# Display.net
KiCad netlist of a schematic drawn in Altium Designer
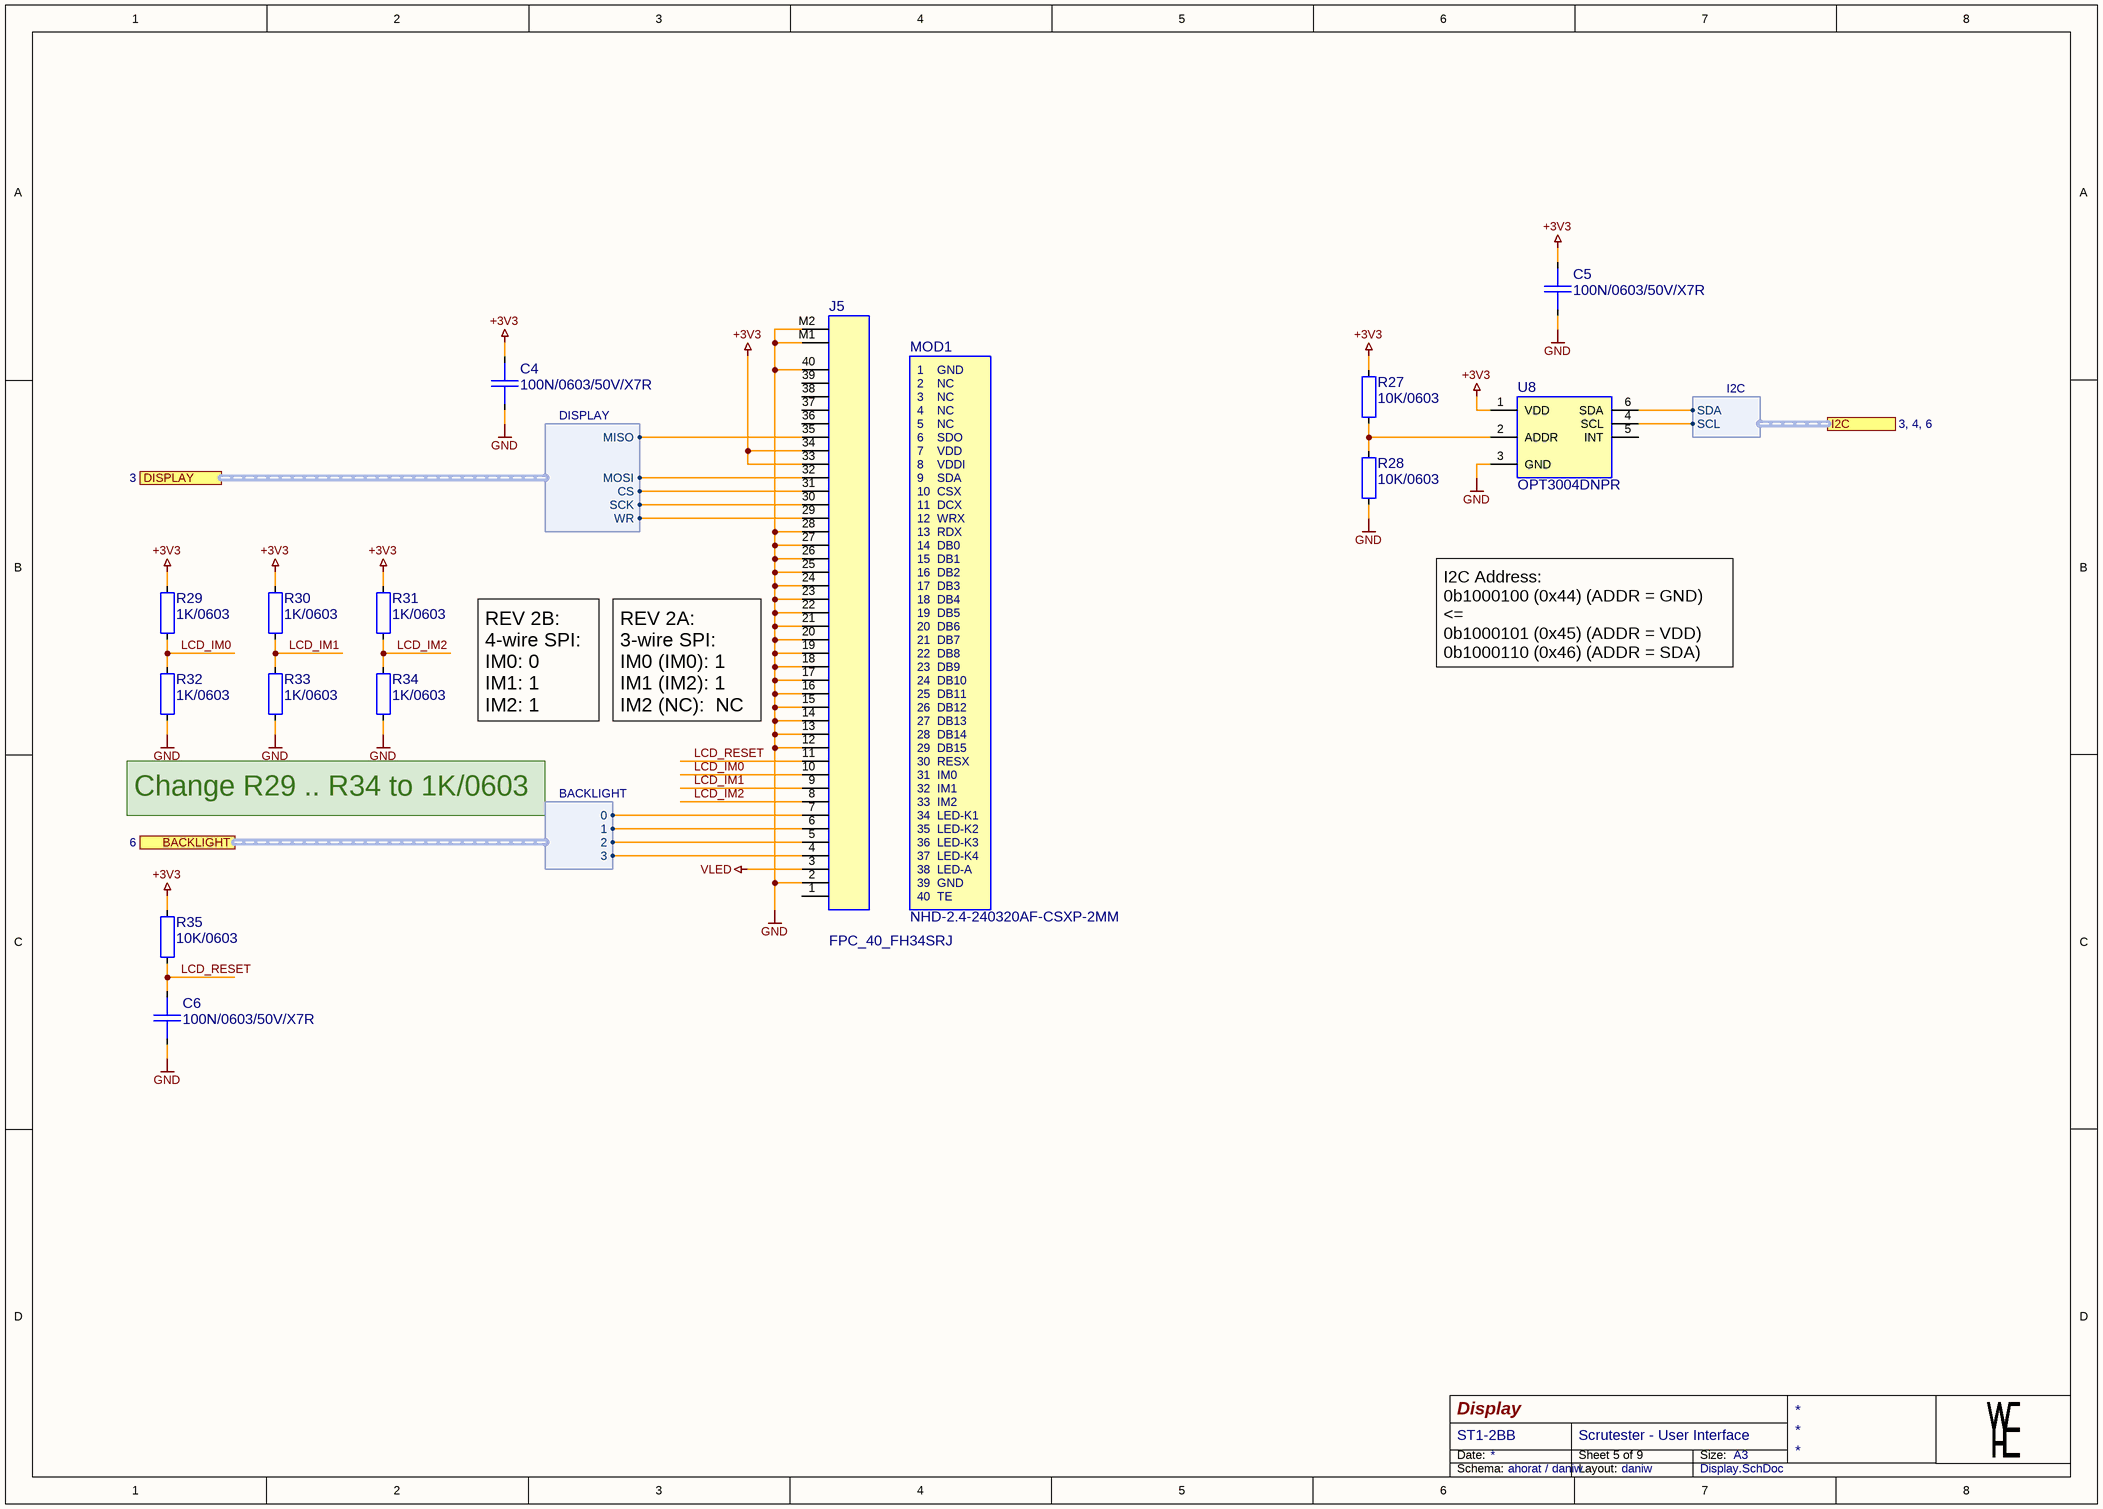
[diagram p0: Display.SchDoc]

(export (version "E")
  (design (tool "Eeschema 10.0.6"))
  (components
    (comp (ref "C4")
      (value "100N/0603/50V/X7R")
      (footprint "CAP0603_X7R")
      (description "CAP SM 0603 100nF 50V X7R")
      (fields (field (name "MANUFACTURER") "GENERIC"))
      (libsource (lib "daniw_altium_lib") (part "C"))
    )
    (comp (ref "C5")
      (value "100N/0603/50V/X7R")
      (footprint "CAP0603_X7R")
      (description "CAP SM 0603 100nF 50V X7R")
      (fields (field (name "MANUFACTURER") "GENERIC"))
      (libsource (lib "daniw_altium_lib") (part "C"))
    )
    (comp (ref "C6")
      (value "100N/0603/50V/X7R")
      (footprint "CAP0603_X7R")
      (description "CAP SM 0603 100nF 50V X7R")
      (fields (field (name "MANUFACTURER") "GENERIC"))
      (libsource (lib "daniw_altium_lib") (part "C"))
    )
    (comp (ref "J5")
      (value "FPC_40_FH34SRJ")
      (footprint "CON_FPC40_FH34SRJ")
      (description "FPC connector, FH34 series, 40 pins")
      (fields (field (name "MANUFACTURER") "Hirose"))
      (libsource (lib "daniw_altium_lib") (part "CON40-2M"))
    )
    (comp (ref "MOD1")
      (value "NHD-2.4-240320AF-CSXP-2MM")
      (footprint "NHD-2.4-240320AF-CSXP-2MM")
      (fields (field (name "MANUFACTURER") "Newhaven Display"))
      (libsource (lib "daniw_altium_lib") (part "NHD-2.4-240320AF-CSXP"))
    )
    (comp (ref "R27")
      (value "10K/0603")
      (footprint "R0603-0.40-WW")
      (description "RES SM 0603 10K")
      (fields (field (name "MANUFACTURER") "GENERIC"))
      (libsource (lib "daniw_altium_lib") (part "R"))
    )
    (comp (ref "R28")
      (value "10K/0603")
      (footprint "R0603-0.40-WW")
      (description "RES SM 0603 10K")
      (fields (field (name "MANUFACTURER") "GENERIC"))
      (libsource (lib "daniw_altium_lib") (part "R"))
    )
    (comp (ref "R29")
      (value "1K/0603")
      (footprint "R0603-0.40-WW")
      (description "RES SM 0603 1K")
      (fields (field (name "MANUFACTURER") "GENERIC"))
      (libsource (lib "daniw_altium_lib") (part "R"))
    )
    (comp (ref "R30")
      (value "1K/0603")
      (footprint "R0603-0.40-WW")
      (description "RES SM 0603 1K")
      (fields (field (name "MANUFACTURER") "GENERIC"))
      (libsource (lib "daniw_altium_lib") (part "R"))
    )
    (comp (ref "R31")
      (value "1K/0603")
      (footprint "R0603-0.40-WW")
      (description "RES SM 0603 1K")
      (fields (field (name "MANUFACTURER") "GENERIC"))
      (libsource (lib "daniw_altium_lib") (part "R"))
    )
    (comp (ref "R32")
      (value "1K/0603")
      (footprint "R0603-0.40-WW")
      (description "RES SM 0603 1K")
      (fields (field (name "MANUFACTURER") "GENERIC"))
      (libsource (lib "daniw_altium_lib") (part "R"))
    )
    (comp (ref "R33")
      (value "1K/0603")
      (footprint "R0603-0.40-WW")
      (description "RES SM 0603 1K")
      (fields (field (name "MANUFACTURER") "GENERIC"))
      (libsource (lib "daniw_altium_lib") (part "R"))
    )
    (comp (ref "R34")
      (value "1K/0603")
      (footprint "R0603-0.40-WW")
      (description "RES SM 0603 1K")
      (fields (field (name "MANUFACTURER") "GENERIC"))
      (libsource (lib "daniw_altium_lib") (part "R"))
    )
    (comp (ref "R35")
      (value "10K/0603")
      (footprint "R0603-0.40-WW")
      (description "RES SM 0603 10K")
      (fields (field (name "MANUFACTURER") "GENERIC"))
      (libsource (lib "daniw_altium_lib") (part "R"))
    )
    (comp (ref "U8")
      (value "OPT3004DNPR")
      (footprint "SON065P200X200X65-6-EP065X130-CLEAR")
      (description "OPT3004DNPR, OPT3004 Ambient Light Sensor (ALS) With Excellent Angular IR Rejection, USON8")
      (fields (field (name "MANUFACTURER") "Texas Instruments"))
      (libsource (lib "daniw_altium_lib") (part "OPT3004_6"))
    )
  )
  (nets
    (net (code "4") (name "+3V3") (class "Default")
      (node (ref "C4") (pin "1") (pinfunction "1_1") (pintype "passive"))
      (node (ref "C5") (pin "1") (pinfunction "1_1") (pintype "passive"))
      (node (ref "J5") (pin "33") (pintype "passive"))
      (node (ref "J5") (pin "34") (pintype "passive"))
      (node (ref "R27") (pin "1") (pinfunction "1_1") (pintype "passive"))
      (node (ref "R29") (pin "1") (pinfunction "1_1") (pintype "passive"))
      (node (ref "R30") (pin "1") (pinfunction "1_1") (pintype "passive"))
      (node (ref "R31") (pin "1") (pinfunction "1_1") (pintype "passive"))
      (node (ref "R35") (pin "1") (pinfunction "1_1") (pintype "passive"))
      (node (ref "U8") (pin "1") (pinfunction "VDD_1") (pintype "passive"))
    )
    (net (code "5") (name "/0") (class "Default") (node (ref "J5") (pin "7") (pintype "passive")))
    (net (code "6") (name "/1") (class "Default") (node (ref "J5") (pin "6") (pintype "passive")))
    (net (code "7") (name "/2") (class "Default") (node (ref "J5") (pin "5") (pintype "passive")))
    (net (code "8") (name "/3") (class "Default") (node (ref "J5") (pin "4") (pintype "passive")))
    (net (code "9") (name "/CS") (class "Default") (node (ref "J5") (pin "31") (pintype "passive")))
    (net (code "10") (name "/LCD_IM0") (class "Default")
      (node (ref "J5") (pin "10") (pintype "passive"))
      (node (ref "R29") (pin "2") (pinfunction "2_2") (pintype "passive"))
      (node (ref "R32") (pin "1") (pinfunction "1_1") (pintype "passive"))
    )
    (net (code "11") (name "/LCD_IM1") (class "Default")
      (node (ref "J5") (pin "9") (pintype "passive"))
      (node (ref "R30") (pin "2") (pinfunction "2_2") (pintype "passive"))
      (node (ref "R33") (pin "1") (pinfunction "1_1") (pintype "passive"))
    )
    (net (code "12") (name "/LCD_IM2") (class "Default")
      (node (ref "J5") (pin "8") (pintype "passive"))
      (node (ref "R31") (pin "2") (pinfunction "2_2") (pintype "passive"))
      (node (ref "R34") (pin "1") (pinfunction "1_1") (pintype "passive"))
    )
    (net (code "13") (name "/LCD_RESET") (class "Default")
      (node (ref "C6") (pin "1") (pinfunction "1_1") (pintype "passive"))
      (node (ref "J5") (pin "11") (pintype "passive"))
      (node (ref "R35") (pin "2") (pinfunction "2_2") (pintype "passive"))
    )
    (net (code "14") (name "/MISO") (class "Default") (node (ref "J5") (pin "35") (pintype "passive")))
    (net (code "15") (name "/MOSI") (class "Default") (node (ref "J5") (pin "32") (pintype "passive")))
    (net (code "16") (name "/SCK") (class "Default") (node (ref "J5") (pin "30") (pintype "passive")))
    (net (code "17") (name "/SCL") (class "Default")
      (node (ref "U8") (pin "4") (pinfunction "SCL_4") (pintype "passive"))
    )
    (net (code "18") (name "/SDA") (class "Default")
      (node (ref "U8") (pin "6") (pinfunction "SDA_6") (pintype "passive"))
    )
    (net (code "19") (name "/WR") (class "Default") (node (ref "J5") (pin "29") (pintype "passive")))
    (net (code "23") (name "GND") (class "Default")
      (node (ref "C4") (pin "2") (pinfunction "2_2") (pintype "passive"))
      (node (ref "C5") (pin "2") (pinfunction "2_2") (pintype "passive"))
      (node (ref "C6") (pin "2") (pinfunction "2_2") (pintype "passive"))
      (node (ref "J5") (pin "12") (pintype "passive"))
      (node (ref "J5") (pin "13") (pintype "passive"))
      (node (ref "J5") (pin "14") (pintype "passive"))
      (node (ref "J5") (pin "15") (pintype "passive"))
      (node (ref "J5") (pin "16") (pintype "passive"))
      (node (ref "J5") (pin "17") (pintype "passive"))
      (node (ref "J5") (pin "18") (pintype "passive"))
      (node (ref "J5") (pin "19") (pintype "passive"))
      (node (ref "J5") (pin "2") (pintype "passive"))
      (node (ref "J5") (pin "20") (pintype "passive"))
      (node (ref "J5") (pin "21") (pintype "passive"))
      (node (ref "J5") (pin "22") (pintype "passive"))
      (node (ref "J5") (pin "23") (pintype "passive"))
      (node (ref "J5") (pin "24") (pintype "passive"))
      (node (ref "J5") (pin "25") (pintype "passive"))
      (node (ref "J5") (pin "26") (pintype "passive"))
      (node (ref "J5") (pin "27") (pintype "passive"))
      (node (ref "J5") (pin "28") (pintype "passive"))
      (node (ref "J5") (pin "40") (pintype "passive"))
      (node (ref "J5") (pin "M1") (pintype "passive"))
      (node (ref "J5") (pin "M2") (pintype "passive"))
      (node (ref "R28") (pin "2") (pinfunction "2_2") (pintype "passive"))
      (node (ref "R32") (pin "2") (pinfunction "2_2") (pintype "passive"))
      (node (ref "R33") (pin "2") (pinfunction "2_2") (pintype "passive"))
      (node (ref "R34") (pin "2") (pinfunction "2_2") (pintype "passive"))
      (node (ref "U8") (pin "3") (pinfunction "GND_3") (pintype "passive"))
    )
    (net (code "24") (name "Net-(U8-ADDR)") (class "Default")
      (node (ref "R27") (pin "2") (pinfunction "2_2") (pintype "passive"))
      (node (ref "R28") (pin "1") (pinfunction "1_1") (pintype "passive"))
      (node (ref "U8") (pin "2") (pinfunction "ADDR_2") (pintype "passive"))
    )
    (net (code "25") (name "VLED") (class "Default") (node (ref "J5") (pin "3") (pintype "passive")))
    (net (code "26") (name "unconnected-(J5-Pad1)") (class "Default")
      (node (ref "J5") (pin "1") (pintype "passive"))
    )
    (net (code "27") (name "unconnected-(J5-Pad36)") (class "Default")
      (node (ref "J5") (pin "36") (pintype "passive"))
    )
    (net (code "28") (name "unconnected-(J5-Pad37)") (class "Default")
      (node (ref "J5") (pin "37") (pintype "passive"))
    )
    (net (code "29") (name "unconnected-(J5-Pad38)") (class "Default")
      (node (ref "J5") (pin "38") (pintype "passive"))
    )
    (net (code "30") (name "unconnected-(J5-Pad39)") (class "Default")
      (node (ref "J5") (pin "39") (pintype "passive"))
    )
    (net (code "31") (name "unconnected-(U8-INT-Pad5)") (class "Default")
      (node (ref "U8") (pin "5") (pinfunction "INT_5") (pintype "passive"))
    )
  )
)
